# Beta24_SMD.net
KiCad netlist of a schematic drawn in EAGLE
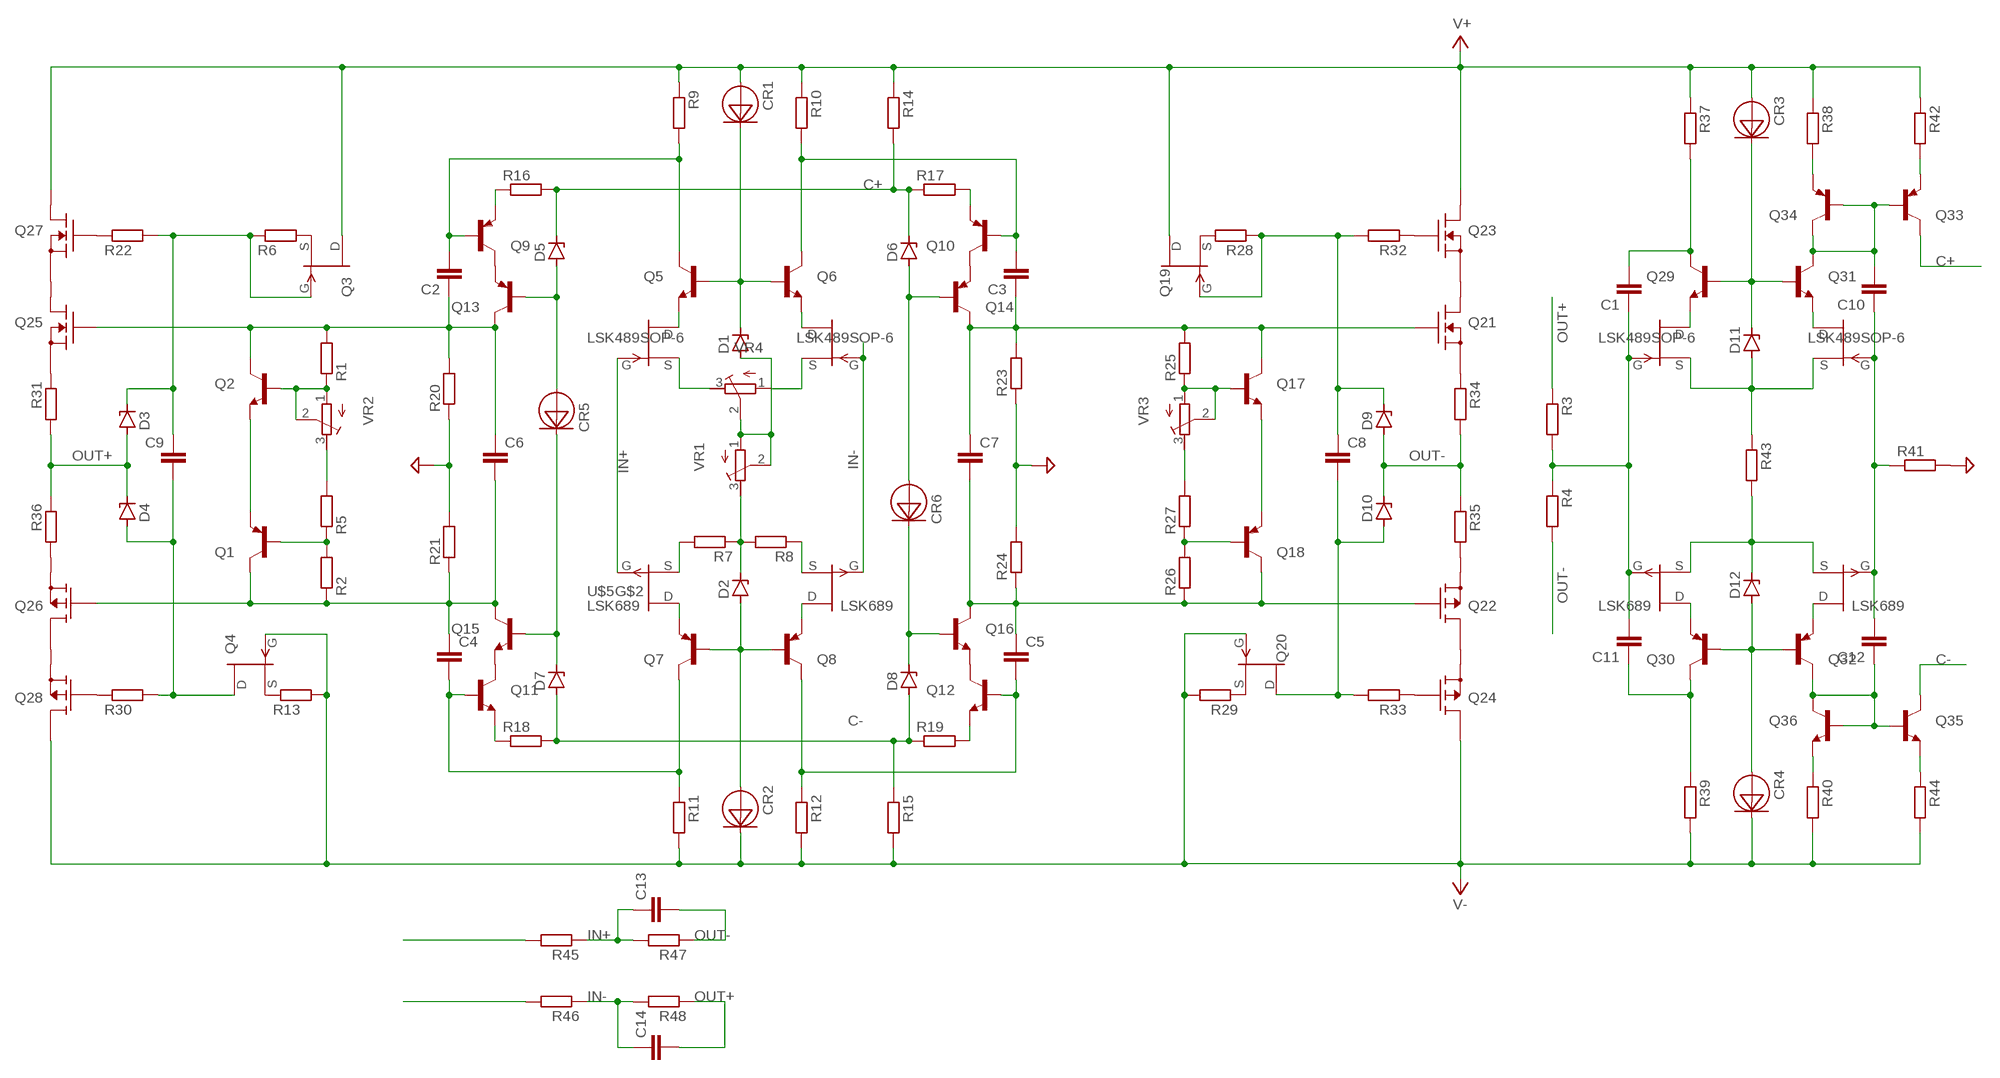
[diagram p0: schematic, sheet 1]

(export (version "E")
  (design (tool "Eeschema 10.0.6"))
  (components
    (comp (ref "C1")
      (value "C-EUC1206")
      (footprint "eagle-import:C1206")
      (libsource (lib "eagle-import") (part "C-EUC1206"))
    )
    (comp (ref "C2")
      (value "C-EUC1206")
      (footprint "eagle-import:C1206")
      (libsource (lib "eagle-import") (part "C-EUC1206"))
    )
    (comp (ref "C3")
      (value "C-EUC1206")
      (footprint "eagle-import:C1206")
      (libsource (lib "eagle-import") (part "C-EUC1206"))
    )
    (comp (ref "C4")
      (value "C-EUC1206")
      (footprint "eagle-import:C1206")
      (libsource (lib "eagle-import") (part "C-EUC1206"))
    )
    (comp (ref "C5")
      (value "C-EUC1206")
      (footprint "eagle-import:C1206")
      (libsource (lib "eagle-import") (part "C-EUC1206"))
    )
    (comp (ref "C6")
      (value "C-EUC1206")
      (footprint "eagle-import:C1206")
      (libsource (lib "eagle-import") (part "C-EUC1206"))
    )
    (comp (ref "C7")
      (value "C-EUC1206")
      (footprint "eagle-import:C1206")
      (libsource (lib "eagle-import") (part "C-EUC1206"))
    )
    (comp (ref "C8")
      (value "C-EUC1206")
      (footprint "eagle-import:C1206")
      (libsource (lib "eagle-import") (part "C-EUC1206"))
    )
    (comp (ref "C9")
      (value "C-EUC1206")
      (footprint "eagle-import:C1206")
      (libsource (lib "eagle-import") (part "C-EUC1206"))
    )
    (comp (ref "C10")
      (value "C-EUC1206")
      (footprint "eagle-import:C1206")
      (libsource (lib "eagle-import") (part "C-EUC1206"))
    )
    (comp (ref "C11")
      (value "C-EUC1206")
      (footprint "eagle-import:C1206")
      (libsource (lib "eagle-import") (part "C-EUC1206"))
    )
    (comp (ref "C12")
      (value "C-EUC1206")
      (footprint "eagle-import:C1206")
      (libsource (lib "eagle-import") (part "C-EUC1206"))
    )
    (comp (ref "C13")
      (value "C-EUC1206")
      (footprint "eagle-import:C1206")
      (libsource (lib "eagle-import") (part "C-EUC1206"))
    )
    (comp (ref "C14")
      (value "C-EUC1206")
      (footprint "eagle-import:C1206")
      (libsource (lib "eagle-import") (part "C-EUC1206"))
    )
    (comp (ref "CR1")
      (value "1N5283")
      (footprint "eagle-import:SMD")
      (libsource (lib "eagle-import") (part "1N5283"))
    )
    (comp (ref "CR2")
      (value "1N5283")
      (footprint "eagle-import:SMD")
      (libsource (lib "eagle-import") (part "1N5283"))
    )
    (comp (ref "CR3")
      (value "1N5283")
      (footprint "eagle-import:SMD")
      (libsource (lib "eagle-import") (part "1N5283"))
    )
    (comp (ref "CR4")
      (value "1N5283")
      (footprint "eagle-import:SMD")
      (libsource (lib "eagle-import") (part "1N5283"))
    )
    (comp (ref "CR5")
      (value "1N5283")
      (footprint "eagle-import:SMD")
      (libsource (lib "eagle-import") (part "1N5283"))
    )
    (comp (ref "CR6")
      (value "1N5283")
      (footprint "eagle-import:SMD")
      (libsource (lib "eagle-import") (part "1N5283"))
    )
    (comp (ref "D1")
      (value "ZENER-DIODESOD80C")
      (footprint "eagle-import:SOD80C")
      (libsource (lib "eagle-import") (part "ZENER-DIODESOD80C"))
    )
    (comp (ref "D2")
      (value "ZENER-DIODESOD80C")
      (footprint "eagle-import:SOD80C")
      (libsource (lib "eagle-import") (part "ZENER-DIODESOD80C"))
    )
    (comp (ref "D3")
      (value "ZENER-DIODESOD80C")
      (footprint "eagle-import:SOD80C")
      (libsource (lib "eagle-import") (part "ZENER-DIODESOD80C"))
    )
    (comp (ref "D4")
      (value "ZENER-DIODESOD80C")
      (footprint "eagle-import:SOD80C")
      (libsource (lib "eagle-import") (part "ZENER-DIODESOD80C"))
    )
    (comp (ref "D5")
      (value "ZENER-DIODESOD80C")
      (footprint "eagle-import:SOD80C")
      (libsource (lib "eagle-import") (part "ZENER-DIODESOD80C"))
    )
    (comp (ref "D6")
      (value "ZENER-DIODESOD80C")
      (footprint "eagle-import:SOD80C")
      (libsource (lib "eagle-import") (part "ZENER-DIODESOD80C"))
    )
    (comp (ref "D7")
      (value "ZENER-DIODESOD80C")
      (footprint "eagle-import:SOD80C")
      (libsource (lib "eagle-import") (part "ZENER-DIODESOD80C"))
    )
    (comp (ref "D8")
      (value "ZENER-DIODESOD80C")
      (footprint "eagle-import:SOD80C")
      (libsource (lib "eagle-import") (part "ZENER-DIODESOD80C"))
    )
    (comp (ref "D9")
      (value "ZENER-DIODESOD80C")
      (footprint "eagle-import:SOD80C")
      (libsource (lib "eagle-import") (part "ZENER-DIODESOD80C"))
    )
    (comp (ref "D10")
      (value "ZENER-DIODESOD80C")
      (footprint "eagle-import:SOD80C")
      (libsource (lib "eagle-import") (part "ZENER-DIODESOD80C"))
    )
    (comp (ref "D11")
      (value "ZENER-DIODESOD80C")
      (footprint "eagle-import:SOD80C")
      (libsource (lib "eagle-import") (part "ZENER-DIODESOD80C"))
    )
    (comp (ref "D12")
      (value "ZENER-DIODESOD80C")
      (footprint "eagle-import:SOD80C")
      (libsource (lib "eagle-import") (part "ZENER-DIODESOD80C"))
    )
    (comp (ref "Q1")
      (value "TRANSISTOR_BC858C-PNP-SOT23-BEC")
      (footprint "eagle-import:TRANSISTOR_SOT23-BEC")
      (libsource (lib "eagle-import") (part "TRANSISTOR_-PNP-SOT23-BECBC858C"))
    )
    (comp (ref "Q2")
      (value "TRANSISTOR_BC850-NPN-SOT23-BEC")
      (footprint "eagle-import:TRANSISTOR_SOT23-BEC")
      (libsource (lib "eagle-import") (part "TRANSISTOR_-NPN-SOT23-BECBC850"))
    )
    (comp (ref "Q3")
      (value "SST5486")
      (footprint "eagle-import:SOT23")
      (libsource (lib "eagle-import") (part "?548SST6"))
    )
    (comp (ref "Q4")
      (value "SST5486")
      (footprint "eagle-import:SOT23")
      (libsource (lib "eagle-import") (part "?548SST6"))
    )
    (comp (ref "Q5")
      (value "TRANSISTOR_BC850-NPN-SOT23-BEC")
      (footprint "eagle-import:TRANSISTOR_SOT23-BEC")
      (libsource (lib "eagle-import") (part "TRANSISTOR_-NPN-SOT23-BECBC850"))
    )
    (comp (ref "Q6")
      (value "TRANSISTOR_BC850-NPN-SOT23-BEC")
      (footprint "eagle-import:TRANSISTOR_SOT23-BEC")
      (libsource (lib "eagle-import") (part "TRANSISTOR_-NPN-SOT23-BECBC850"))
    )
    (comp (ref "Q7")
      (value "TRANSISTOR_BC858C-PNP-SOT23-BEC")
      (footprint "eagle-import:TRANSISTOR_SOT23-BEC")
      (libsource (lib "eagle-import") (part "TRANSISTOR_-PNP-SOT23-BECBC858C"))
    )
    (comp (ref "Q8")
      (value "TRANSISTOR_BC858C-PNP-SOT23-BEC")
      (footprint "eagle-import:TRANSISTOR_SOT23-BEC")
      (libsource (lib "eagle-import") (part "TRANSISTOR_-PNP-SOT23-BECBC858C"))
    )
    (comp (ref "Q9")
      (value "TRANSISTOR_BC858C-PNP-SOT23-BEC")
      (footprint "eagle-import:TRANSISTOR_SOT23-BEC")
      (libsource (lib "eagle-import") (part "TRANSISTOR_-PNP-SOT23-BECBC858C"))
    )
    (comp (ref "Q10")
      (value "TRANSISTOR_BC858C-PNP-SOT23-BEC")
      (footprint "eagle-import:TRANSISTOR_SOT23-BEC")
      (libsource (lib "eagle-import") (part "TRANSISTOR_-PNP-SOT23-BECBC858C"))
    )
    (comp (ref "Q11")
      (value "TRANSISTOR_BC850-NPN-SOT23-BEC")
      (footprint "eagle-import:TRANSISTOR_SOT23-BEC")
      (libsource (lib "eagle-import") (part "TRANSISTOR_-NPN-SOT23-BECBC850"))
    )
    (comp (ref "Q12")
      (value "TRANSISTOR_BC850-NPN-SOT23-BEC")
      (footprint "eagle-import:TRANSISTOR_SOT23-BEC")
      (libsource (lib "eagle-import") (part "TRANSISTOR_-NPN-SOT23-BECBC850"))
    )
    (comp (ref "Q13")
      (value "TRANSISTOR_BC858C-PNP-SOT23-BEC")
      (footprint "eagle-import:TRANSISTOR_SOT23-BEC")
      (libsource (lib "eagle-import") (part "TRANSISTOR_-PNP-SOT23-BECBC858C"))
    )
    (comp (ref "Q14")
      (value "TRANSISTOR_BC858C-PNP-SOT23-BEC")
      (footprint "eagle-import:TRANSISTOR_SOT23-BEC")
      (libsource (lib "eagle-import") (part "TRANSISTOR_-PNP-SOT23-BECBC858C"))
    )
    (comp (ref "Q15")
      (value "TRANSISTOR_BC850-NPN-SOT23-BEC")
      (footprint "eagle-import:TRANSISTOR_SOT23-BEC")
      (libsource (lib "eagle-import") (part "TRANSISTOR_-NPN-SOT23-BECBC850"))
    )
    (comp (ref "Q16")
      (value "TRANSISTOR_BC850-NPN-SOT23-BEC")
      (footprint "eagle-import:TRANSISTOR_SOT23-BEC")
      (libsource (lib "eagle-import") (part "TRANSISTOR_-NPN-SOT23-BECBC850"))
    )
    (comp (ref "Q17")
      (value "TRANSISTOR_BC850-NPN-SOT23-BEC")
      (footprint "eagle-import:TRANSISTOR_SOT23-BEC")
      (libsource (lib "eagle-import") (part "TRANSISTOR_-NPN-SOT23-BECBC850"))
    )
    (comp (ref "Q18")
      (value "TRANSISTOR_BC858C-PNP-SOT23-BEC")
      (footprint "eagle-import:TRANSISTOR_SOT23-BEC")
      (libsource (lib "eagle-import") (part "TRANSISTOR_-PNP-SOT23-BECBC858C"))
    )
    (comp (ref "Q19")
      (value "SST5486")
      (footprint "eagle-import:SOT23")
      (libsource (lib "eagle-import") (part "?548SST6"))
    )
    (comp (ref "Q20")
      (value "SST5486")
      (footprint "eagle-import:SOT23")
      (libsource (lib "eagle-import") (part "?548SST6"))
    )
    (comp (ref "Q21")
      (value "IRFZ24N")
      (footprint "eagle-import:TO220V")
      (libsource (lib "eagle-import") (part "IRFZ24N"))
    )
    (comp (ref "Q22")
      (value "IRFZ34N")
      (footprint "eagle-import:TO220V")
      (libsource (lib "eagle-import") (part "IRFZ34N"))
    )
    (comp (ref "Q23")
      (value "IRFZ24N")
      (footprint "eagle-import:TO220V")
      (libsource (lib "eagle-import") (part "IRFZ24N"))
    )
    (comp (ref "Q24")
      (value "IRFZ34N")
      (footprint "eagle-import:TO220V")
      (libsource (lib "eagle-import") (part "IRFZ34N"))
    )
    (comp (ref "Q25")
      (value "IRFZ24N")
      (footprint "eagle-import:TO220V")
      (libsource (lib "eagle-import") (part "IRFZ24N"))
    )
    (comp (ref "Q26")
      (value "IRFZ34N")
      (footprint "eagle-import:TO220V")
      (libsource (lib "eagle-import") (part "IRFZ34N"))
    )
    (comp (ref "Q27")
      (value "IRFZ24N")
      (footprint "eagle-import:TO220V")
      (libsource (lib "eagle-import") (part "IRFZ24N"))
    )
    (comp (ref "Q28")
      (value "IRFZ34N")
      (footprint "eagle-import:TO220V")
      (libsource (lib "eagle-import") (part "IRFZ34N"))
    )
    (comp (ref "Q29")
      (value "TRANSISTOR_BC850-NPN-SOT23-BEC")
      (footprint "eagle-import:TRANSISTOR_SOT23-BEC")
      (libsource (lib "eagle-import") (part "TRANSISTOR_-NPN-SOT23-BECBC850"))
    )
    (comp (ref "Q30")
      (value "TRANSISTOR_BC858C-PNP-SOT23-BEC")
      (footprint "eagle-import:TRANSISTOR_SOT23-BEC")
      (libsource (lib "eagle-import") (part "TRANSISTOR_-PNP-SOT23-BECBC858C"))
    )
    (comp (ref "Q31")
      (value "TRANSISTOR_BC850-NPN-SOT23-BEC")
      (footprint "eagle-import:TRANSISTOR_SOT23-BEC")
      (libsource (lib "eagle-import") (part "TRANSISTOR_-NPN-SOT23-BECBC850"))
    )
    (comp (ref "Q32")
      (value "TRANSISTOR_BC858C-PNP-SOT23-BEC")
      (footprint "eagle-import:TRANSISTOR_SOT23-BEC")
      (libsource (lib "eagle-import") (part "TRANSISTOR_-PNP-SOT23-BECBC858C"))
    )
    (comp (ref "Q33")
      (value "TRANSISTOR_BC858C-PNP-SOT23-BEC")
      (footprint "eagle-import:TRANSISTOR_SOT23-BEC")
      (libsource (lib "eagle-import") (part "TRANSISTOR_-PNP-SOT23-BECBC858C"))
    )
    (comp (ref "Q34")
      (value "TRANSISTOR_BC858C-PNP-SOT23-BEC")
      (footprint "eagle-import:TRANSISTOR_SOT23-BEC")
      (libsource (lib "eagle-import") (part "TRANSISTOR_-PNP-SOT23-BECBC858C"))
    )
    (comp (ref "Q35")
      (value "TRANSISTOR_BC850-NPN-SOT23-BEC")
      (footprint "eagle-import:TRANSISTOR_SOT23-BEC")
      (libsource (lib "eagle-import") (part "TRANSISTOR_-NPN-SOT23-BECBC850"))
    )
    (comp (ref "Q36")
      (value "TRANSISTOR_BC850-NPN-SOT23-BEC")
      (footprint "eagle-import:TRANSISTOR_SOT23-BEC")
      (libsource (lib "eagle-import") (part "TRANSISTOR_-NPN-SOT23-BECBC850"))
    )
    (comp (ref "R1")
      (value "R-EU_MELF0204W")
      (footprint "eagle-import:MINI_MELF-0204W")
      (libsource (lib "eagle-import") (part "R-EU_MELF0204W"))
    )
    (comp (ref "R2")
      (value "R-EU_MELF0204W")
      (footprint "eagle-import:MINI_MELF-0204W")
      (libsource (lib "eagle-import") (part "R-EU_MELF0204W"))
    )
    (comp (ref "R3")
      (value "R-EU_MELF0204W")
      (footprint "eagle-import:MINI_MELF-0204W")
      (libsource (lib "eagle-import") (part "R-EU_MELF0204W"))
    )
    (comp (ref "R4")
      (value "R-EU_MELF0204W")
      (footprint "eagle-import:MINI_MELF-0204W")
      (libsource (lib "eagle-import") (part "R-EU_MELF0204W"))
    )
    (comp (ref "R5")
      (value "R-EU_MELF0204W")
      (footprint "eagle-import:MINI_MELF-0204W")
      (libsource (lib "eagle-import") (part "R-EU_MELF0204W"))
    )
    (comp (ref "R6")
      (value "R-EU_MELF0204W")
      (footprint "eagle-import:MINI_MELF-0204W")
      (libsource (lib "eagle-import") (part "R-EU_MELF0204W"))
    )
    (comp (ref "R7")
      (value "R-EU_MELF0204W")
      (footprint "eagle-import:MINI_MELF-0204W")
      (libsource (lib "eagle-import") (part "R-EU_MELF0204W"))
    )
    (comp (ref "R8")
      (value "R-EU_MELF0204W")
      (footprint "eagle-import:MINI_MELF-0204W")
      (libsource (lib "eagle-import") (part "R-EU_MELF0204W"))
    )
    (comp (ref "R9")
      (value "R-EU_MELF0204W")
      (footprint "eagle-import:MINI_MELF-0204W")
      (libsource (lib "eagle-import") (part "R-EU_MELF0204W"))
    )
    (comp (ref "R10")
      (value "R-EU_MELF0204W")
      (footprint "eagle-import:MINI_MELF-0204W")
      (libsource (lib "eagle-import") (part "R-EU_MELF0204W"))
    )
    (comp (ref "R11")
      (value "R-EU_MELF0204W")
      (footprint "eagle-import:MINI_MELF-0204W")
      (libsource (lib "eagle-import") (part "R-EU_MELF0204W"))
    )
    (comp (ref "R12")
      (value "R-EU_MELF0204W")
      (footprint "eagle-import:MINI_MELF-0204W")
      (libsource (lib "eagle-import") (part "R-EU_MELF0204W"))
    )
    (comp (ref "R13")
      (value "R-EU_MELF0204W")
      (footprint "eagle-import:MINI_MELF-0204W")
      (libsource (lib "eagle-import") (part "R-EU_MELF0204W"))
    )
    (comp (ref "R14")
      (value "R-EU_MELF0204W")
      (footprint "eagle-import:MINI_MELF-0204W")
      (libsource (lib "eagle-import") (part "R-EU_MELF0204W"))
    )
    (comp (ref "R15")
      (value "R-EU_MELF0204W")
      (footprint "eagle-import:MINI_MELF-0204W")
      (libsource (lib "eagle-import") (part "R-EU_MELF0204W"))
    )
    (comp (ref "R16")
      (value "R-EU_MELF0204W")
      (footprint "eagle-import:MINI_MELF-0204W")
      (libsource (lib "eagle-import") (part "R-EU_MELF0204W"))
    )
    (comp (ref "R17")
      (value "R-EU_MELF0204W")
      (footprint "eagle-import:MINI_MELF-0204W")
      (libsource (lib "eagle-import") (part "R-EU_MELF0204W"))
    )
    (comp (ref "R18")
      (value "R-EU_MELF0204W")
      (footprint "eagle-import:MINI_MELF-0204W")
      (libsource (lib "eagle-import") (part "R-EU_MELF0204W"))
    )
    (comp (ref "R19")
      (value "R-EU_MELF0204W")
      (footprint "eagle-import:MINI_MELF-0204W")
      (libsource (lib "eagle-import") (part "R-EU_MELF0204W"))
    )
    (comp (ref "R20")
      (value "R-EU_MELF0204W")
      (footprint "eagle-import:MINI_MELF-0204W")
      (libsource (lib "eagle-import") (part "R-EU_MELF0204W"))
    )
    (comp (ref "R21")
      (value "R-EU_MELF0204W")
      (footprint "eagle-import:MINI_MELF-0204W")
      (libsource (lib "eagle-import") (part "R-EU_MELF0204W"))
    )
    (comp (ref "R22")
      (value "R-EU_MELF0204W")
      (footprint "eagle-import:MINI_MELF-0204W")
      (libsource (lib "eagle-import") (part "R-EU_MELF0204W"))
    )
    (comp (ref "R23")
      (value "R-EU_MELF0204W")
      (footprint "eagle-import:MINI_MELF-0204W")
      (libsource (lib "eagle-import") (part "R-EU_MELF0204W"))
    )
    (comp (ref "R24")
      (value "R-EU_MELF0204W")
      (footprint "eagle-import:MINI_MELF-0204W")
      (libsource (lib "eagle-import") (part "R-EU_MELF0204W"))
    )
    (comp (ref "R25")
      (value "R-EU_MELF0204W")
      (footprint "eagle-import:MINI_MELF-0204W")
      (libsource (lib "eagle-import") (part "R-EU_MELF0204W"))
    )
    (comp (ref "R26")
      (value "R-EU_MELF0204W")
      (footprint "eagle-import:MINI_MELF-0204W")
      (libsource (lib "eagle-import") (part "R-EU_MELF0204W"))
    )
    (comp (ref "R27")
      (value "R-EU_MELF0204W")
      (footprint "eagle-import:MINI_MELF-0204W")
      (libsource (lib "eagle-import") (part "R-EU_MELF0204W"))
    )
    (comp (ref "R28")
      (value "R-EU_MELF0204W")
      (footprint "eagle-import:MINI_MELF-0204W")
      (libsource (lib "eagle-import") (part "R-EU_MELF0204W"))
    )
    (comp (ref "R29")
      (value "R-EU_MELF0204W")
      (footprint "eagle-import:MINI_MELF-0204W")
      (libsource (lib "eagle-import") (part "R-EU_MELF0204W"))
    )
    (comp (ref "R30")
      (value "R-EU_MELF0204W")
      (footprint "eagle-import:MINI_MELF-0204W")
      (libsource (lib "eagle-import") (part "R-EU_MELF0204W"))
    )
    (comp (ref "R31")
      (value "R-EU_0617/17")
      (footprint "eagle-import:0617_17")
      (libsource (lib "eagle-import") (part "R-EU_0617/17"))
    )
    (comp (ref "R32")
      (value "R-EU_MELF0204W")
      (footprint "eagle-import:MINI_MELF-0204W")
      (libsource (lib "eagle-import") (part "R-EU_MELF0204W"))
    )
    (comp (ref "R33")
      (value "R-EU_MELF0204W")
      (footprint "eagle-import:MINI_MELF-0204W")
      (libsource (lib "eagle-import") (part "R-EU_MELF0204W"))
    )
    (comp (ref "R34")
      (value "R-EU_0617/17")
      (footprint "eagle-import:0617_17")
      (libsource (lib "eagle-import") (part "R-EU_0617/17"))
    )
    (comp (ref "R35")
      (value "R-EU_0617/17")
      (footprint "eagle-import:0617_17")
      (libsource (lib "eagle-import") (part "R-EU_0617/17"))
    )
    (comp (ref "R36")
      (value "R-EU_0617/17")
      (footprint "eagle-import:0617_17")
      (libsource (lib "eagle-import") (part "R-EU_0617/17"))
    )
    (comp (ref "R37")
      (value "R-EU_MELF0204W")
      (footprint "eagle-import:MINI_MELF-0204W")
      (libsource (lib "eagle-import") (part "R-EU_MELF0204W"))
    )
    (comp (ref "R38")
      (value "R-EU_MELF0204W")
      (footprint "eagle-import:MINI_MELF-0204W")
      (libsource (lib "eagle-import") (part "R-EU_MELF0204W"))
    )
    (comp (ref "R39")
      (value "R-EU_MELF0204W")
      (footprint "eagle-import:MINI_MELF-0204W")
      (libsource (lib "eagle-import") (part "R-EU_MELF0204W"))
    )
    (comp (ref "R40")
      (value "R-EU_MELF0204W")
      (footprint "eagle-import:MINI_MELF-0204W")
      (libsource (lib "eagle-import") (part "R-EU_MELF0204W"))
    )
    (comp (ref "R41")
      (value "R-EU_MELF0204W")
      (footprint "eagle-import:MINI_MELF-0204W")
      (libsource (lib "eagle-import") (part "R-EU_MELF0204W"))
    )
    (comp (ref "R42")
      (value "R-EU_MELF0204W")
      (footprint "eagle-import:MINI_MELF-0204W")
      (libsource (lib "eagle-import") (part "R-EU_MELF0204W"))
    )
    (comp (ref "R43")
      (value "R-EU_MELF0204W")
      (footprint "eagle-import:MINI_MELF-0204W")
      (libsource (lib "eagle-import") (part "R-EU_MELF0204W"))
    )
    (comp (ref "R44")
      (value "R-EU_MELF0204W")
      (footprint "eagle-import:MINI_MELF-0204W")
      (libsource (lib "eagle-import") (part "R-EU_MELF0204W"))
    )
    (comp (ref "R45")
      (value "R-EU_MELF0204W")
      (footprint "eagle-import:MINI_MELF-0204W")
      (libsource (lib "eagle-import") (part "R-EU_MELF0204W"))
    )
    (comp (ref "R46")
      (value "R-EU_MELF0204W")
      (footprint "eagle-import:MINI_MELF-0204W")
      (libsource (lib "eagle-import") (part "R-EU_MELF0204W"))
    )
    (comp (ref "R47")
      (value "R-EU_MELF0204W")
      (footprint "eagle-import:MINI_MELF-0204W")
      (libsource (lib "eagle-import") (part "R-EU_MELF0204W"))
    )
    (comp (ref "R48")
      (value "R-EU_MELF0204W")
      (footprint "eagle-import:MINI_MELF-0204W")
      (libsource (lib "eagle-import") (part "R-EU_MELF0204W"))
    )
    (comp (ref "U$1")
      (value "LSK489SOP-6")
      (footprint "eagle-import:SOT-23-6")
      (libsource (lib "eagle-import") (part "LSK489SOP-6"))
    )
    (comp (ref "U$3")
      (value "LSK489SOP-6")
      (footprint "eagle-import:SOT-23-6")
      (libsource (lib "eagle-import") (part "LSK489SOP-6"))
    )
    (comp (ref "U$4")
      (value "LSK689")
      (footprint "eagle-import:SOT-23-6")
      (libsource (lib "eagle-import") (part "LSK689"))
    )
    (comp (ref "U$5")
      (value "LSK689")
      (footprint "eagle-import:SOT-23-6")
      (libsource (lib "eagle-import") (part "LSK689"))
    )
    (comp (ref "VR1")
      (value "R-TRIMM3296W")
      (footprint "eagle-import:RTRIM3296W")
      (libsource (lib "eagle-import") (part "R-TRIMM3296W"))
    )
    (comp (ref "VR2")
      (value "R-TRIMM3296W")
      (footprint "eagle-import:RTRIM3296W")
      (libsource (lib "eagle-import") (part "R-TRIMM3296W"))
    )
    (comp (ref "VR3")
      (value "R-TRIMM3296W")
      (footprint "eagle-import:RTRIM3296W")
      (libsource (lib "eagle-import") (part "R-TRIMM3296W"))
    )
    (comp (ref "VR4")
      (value "R-TRIMM3296W")
      (footprint "eagle-import:RTRIM3296W")
      (libsource (lib "eagle-import") (part "R-TRIMM3296W"))
    )
  )
  (nets
    (net (code "1") (name "/C+") (class "Default")
      (node (ref "D5") (pin "C") (pinfunction "C_C") (pintype "passive"))
      (node (ref "D6") (pin "C") (pinfunction "C_C") (pintype "passive"))
      (node (ref "Q33") (pin "C") (pinfunction "C_C") (pintype "passive"))
      (node (ref "R14") (pin "2") (pinfunction "2_2") (pintype "passive"))
      (node (ref "R16") (pin "2") (pinfunction "2_2") (pintype "passive"))
      (node (ref "R17") (pin "1") (pinfunction "1_1") (pintype "passive"))
    )
    (net (code "2") (name "/C-") (class "Default")
      (node (ref "D7") (pin "A") (pinfunction "A_A") (pintype "passive"))
      (node (ref "D8") (pin "A") (pinfunction "A_A") (pintype "passive"))
      (node (ref "Q35") (pin "C") (pinfunction "C_C") (pintype "passive"))
      (node (ref "R15") (pin "1") (pinfunction "1_1") (pintype "passive"))
      (node (ref "R18") (pin "2") (pinfunction "2_2") (pintype "passive"))
      (node (ref "R19") (pin "1") (pinfunction "1_1") (pintype "passive"))
    )
    (net (code "3") (name "/IN+") (class "Default")
      (node (ref "C13") (pin "1") (pinfunction "1_1") (pintype "passive"))
      (node (ref "R45") (pin "1") (pinfunction "1_1") (pintype "passive"))
      (node (ref "R47") (pin "2") (pinfunction "2_2") (pintype "passive"))
      (node (ref "U$1") (pin "1") (pinfunction "G_1") (pintype "passive"))
      (node (ref "U$5") (pin "4") (pinfunction "G_4") (pintype "passive"))
    )
    (net (code "4") (name "/IN-") (class "Default")
      (node (ref "C14") (pin "1") (pinfunction "1_1") (pintype "passive"))
      (node (ref "R46") (pin "1") (pinfunction "1_1") (pintype "passive"))
      (node (ref "R48") (pin "2") (pinfunction "2_2") (pintype "passive"))
      (node (ref "U$1") (pin "4") (pinfunction "G_4") (pintype "passive"))
      (node (ref "U$5") (pin "1") (pinfunction "G_1") (pintype "passive"))
    )
    (net (code "5") (name "/OUT+") (class "Default")
      (node (ref "C14") (pin "2") (pinfunction "2_2") (pintype "passive"))
      (node (ref "D3") (pin "A") (pinfunction "A_A") (pintype "passive"))
      (node (ref "D4") (pin "C") (pinfunction "C_C") (pintype "passive"))
      (node (ref "R3") (pin "1") (pinfunction "1_1") (pintype "passive"))
      (node (ref "R31") (pin "2") (pinfunction "2_2") (pintype "passive"))
      (node (ref "R36") (pin "1") (pinfunction "1_1") (pintype "passive"))
      (node (ref "R48") (pin "1") (pinfunction "1_1") (pintype "passive"))
    )
    (net (code "6") (name "/OUT-") (class "Default")
      (node (ref "C13") (pin "2") (pinfunction "2_2") (pintype "passive"))
      (node (ref "D10") (pin "C") (pinfunction "C_C") (pintype "passive"))
      (node (ref "D9") (pin "A") (pinfunction "A_A") (pintype "passive"))
      (node (ref "R34") (pin "2") (pinfunction "2_2") (pintype "passive"))
      (node (ref "R35") (pin "1") (pinfunction "1_1") (pintype "passive"))
      (node (ref "R4") (pin "2") (pinfunction "2_2") (pintype "passive"))
      (node (ref "R47") (pin "1") (pinfunction "1_1") (pintype "passive"))
    )
    (net (code "7") (name "GND") (class "Default")
      (node (ref "R20") (pin "1") (pinfunction "1_1") (pintype "passive"))
      (node (ref "R21") (pin "2") (pinfunction "2_2") (pintype "passive"))
      (node (ref "R23") (pin "1") (pinfunction "1_1") (pintype "passive"))
      (node (ref "R24") (pin "2") (pinfunction "2_2") (pintype "passive"))
      (node (ref "R41") (pin "2") (pinfunction "2_2") (pintype "passive"))
    )
    (net (code "8") (name "Net-(C1-Pad2)") (class "Default")
      (node (ref "C1") (pin "2") (pinfunction "2_2") (pintype "passive"))
      (node (ref "Q29") (pin "C") (pinfunction "C_C") (pintype "passive"))
      (node (ref "R37") (pin "2") (pinfunction "2_2") (pintype "passive"))
    )
    (net (code "9") (name "Net-(C2-Pad2)") (class "Default")
      (node (ref "C2") (pin "2") (pinfunction "2_2") (pintype "passive"))
      (node (ref "Q5") (pin "C") (pinfunction "C_C") (pintype "passive"))
      (node (ref "Q9") (pin "B") (pinfunction "B_B") (pintype "passive"))
      (node (ref "R9") (pin "2") (pinfunction "2_2") (pintype "passive"))
    )
    (net (code "10") (name "Net-(C3-Pad2)") (class "Default")
      (node (ref "C3") (pin "2") (pinfunction "2_2") (pintype "passive"))
      (node (ref "Q10") (pin "B") (pinfunction "B_B") (pintype "passive"))
      (node (ref "Q6") (pin "C") (pinfunction "C_C") (pintype "passive"))
      (node (ref "R10") (pin "2") (pinfunction "2_2") (pintype "passive"))
    )
    (net (code "11") (name "Net-(C4-Pad2)") (class "Default")
      (node (ref "C4") (pin "2") (pinfunction "2_2") (pintype "passive"))
      (node (ref "Q11") (pin "B") (pinfunction "B_B") (pintype "passive"))
      (node (ref "Q7") (pin "C") (pinfunction "C_C") (pintype "passive"))
      (node (ref "R11") (pin "1") (pinfunction "1_1") (pintype "passive"))
    )
    (net (code "12") (name "Net-(C5-Pad2)") (class "Default")
      (node (ref "C5") (pin "2") (pinfunction "2_2") (pintype "passive"))
      (node (ref "Q12") (pin "B") (pinfunction "B_B") (pintype "passive"))
      (node (ref "Q8") (pin "C") (pinfunction "C_C") (pintype "passive"))
      (node (ref "R12") (pin "1") (pinfunction "1_1") (pintype "passive"))
    )
    (net (code "13") (name "Net-(C10-Pad2)") (class "Default")
      (node (ref "C10") (pin "2") (pinfunction "2_2") (pintype "passive"))
      (node (ref "Q31") (pin "C") (pinfunction "C_C") (pintype "passive"))
      (node (ref "Q33") (pin "B") (pinfunction "B_B") (pintype "passive"))
      (node (ref "Q34") (pin "B") (pinfunction "B_B") (pintype "passive"))
      (node (ref "Q34") (pin "C") (pinfunction "C_C") (pintype "passive"))
    )
    (net (code "14") (name "Net-(C11-Pad1)") (class "Default")
      (node (ref "C11") (pin "1") (pinfunction "1_1") (pintype "passive"))
      (node (ref "Q30") (pin "C") (pinfunction "C_C") (pintype "passive"))
      (node (ref "R39") (pin "1") (pinfunction "1_1") (pintype "passive"))
    )
    (net (code "15") (name "Net-(C12-Pad1)") (class "Default")
      (node (ref "C12") (pin "1") (pinfunction "1_1") (pintype "passive"))
      (node (ref "Q32") (pin "C") (pinfunction "C_C") (pintype "passive"))
      (node (ref "Q35") (pin "B") (pinfunction "B_B") (pintype "passive"))
      (node (ref "Q36") (pin "B") (pinfunction "B_B") (pintype "passive"))
      (node (ref "Q36") (pin "C") (pinfunction "C_C") (pintype "passive"))
    )
    (net (code "16") (name "Net-(CR1-PadCATHODE)") (class "Default")
      (node (ref "CR1") (pin "CATHODE") (pinfunction "CATHODE_CATHODE") (pintype "passive"))
      (node (ref "D1") (pin "C") (pinfunction "C_C") (pintype "passive"))
      (node (ref "Q5") (pin "B") (pinfunction "B_B") (pintype "passive"))
      (node (ref "Q6") (pin "B") (pinfunction "B_B") (pintype "passive"))
    )
    (net (code "17") (name "Net-(CR2-PadANODE)") (class "Default")
      (node (ref "CR2") (pin "ANODE") (pinfunction "ANODE_ANODE") (pintype "passive"))
      (node (ref "D2") (pin "A") (pinfunction "A_A") (pintype "passive"))
      (node (ref "Q7") (pin "B") (pinfunction "B_B") (pintype "passive"))
      (node (ref "Q8") (pin "B") (pinfunction "B_B") (pintype "passive"))
    )
    (net (code "18") (name "Net-(CR3-PadCATHODE)") (class "Default")
      (node (ref "CR3") (pin "CATHODE") (pinfunction "CATHODE_CATHODE") (pintype "passive"))
      (node (ref "D11") (pin "C") (pinfunction "C_C") (pintype "passive"))
      (node (ref "Q29") (pin "B") (pinfunction "B_B") (pintype "passive"))
      (node (ref "Q31") (pin "B") (pinfunction "B_B") (pintype "passive"))
    )
    (net (code "19") (name "Net-(CR4-PadANODE)") (class "Default")
      (node (ref "CR4") (pin "ANODE") (pinfunction "ANODE_ANODE") (pintype "passive"))
      (node (ref "D12") (pin "A") (pinfunction "A_A") (pintype "passive"))
      (node (ref "Q30") (pin "B") (pinfunction "B_B") (pintype "passive"))
      (node (ref "Q32") (pin "B") (pinfunction "B_B") (pintype "passive"))
    )
    (net (code "20") (name "Net-(CR5-PadANODE)") (class "Default")
      (node (ref "CR5") (pin "ANODE") (pinfunction "ANODE_ANODE") (pintype "passive"))
      (node (ref "D5") (pin "A") (pinfunction "A_A") (pintype "passive"))
      (node (ref "Q13") (pin "B") (pinfunction "B_B") (pintype "passive"))
    )
    (net (code "21") (name "Net-(CR5-PadCATHODE)") (class "Default")
      (node (ref "CR5") (pin "CATHODE") (pinfunction "CATHODE_CATHODE") (pintype "passive"))
      (node (ref "D7") (pin "C") (pinfunction "C_C") (pintype "passive"))
      (node (ref "Q15") (pin "B") (pinfunction "B_B") (pintype "passive"))
    )
    (net (code "22") (name "Net-(CR6-PadANODE)") (class "Default")
      (node (ref "CR6") (pin "ANODE") (pinfunction "ANODE_ANODE") (pintype "passive"))
      (node (ref "D6") (pin "A") (pinfunction "A_A") (pintype "passive"))
      (node (ref "Q14") (pin "B") (pinfunction "B_B") (pintype "passive"))
    )
    (net (code "23") (name "Net-(CR6-PadCATHODE)") (class "Default")
      (node (ref "CR6") (pin "CATHODE") (pinfunction "CATHODE_CATHODE") (pintype "passive"))
      (node (ref "D8") (pin "C") (pinfunction "C_C") (pintype "passive"))
      (node (ref "Q16") (pin "B") (pinfunction "B_B") (pintype "passive"))
    )
    (net (code "24") (name "Net-(Q1-PadB)") (class "Default")
      (node (ref "Q1") (pin "B") (pinfunction "B_B") (pintype "passive"))
      (node (ref "R2") (pin "2") (pinfunction "2_2") (pintype "passive"))
      (node (ref "R5") (pin "1") (pinfunction "1_1") (pintype "passive"))
    )
    (net (code "25") (name "Net-(Q1-PadE)") (class "Default")
      (node (ref "Q1") (pin "E") (pinfunction "E_E") (pintype "passive"))
      (node (ref "Q2") (pin "E") (pinfunction "E_E") (pintype "passive"))
    )
    (net (code "26") (name "Net-(Q3-G)") (class "Default")
      (node (ref "C9") (pin "1") (pinfunction "1_1") (pintype "passive"))
      (node (ref "D3") (pin "C") (pinfunction "C_C") (pintype "passive"))
      (node (ref "Q3") (pin "3") (pinfunction "G_3") (pintype "passive"))
      (node (ref "R22") (pin "2") (pinfunction "2_2") (pintype "passive"))
      (node (ref "R6") (pin "1") (pinfunction "1_1") (pintype "passive"))
    )
    (net (code "27") (name "Net-(Q3-S)") (class "Default")
      (node (ref "Q3") (pin "2") (pinfunction "S_2") (pintype "passive"))
      (node (ref "R6") (pin "2") (pinfunction "2_2") (pintype "passive"))
    )
    (net (code "28") (name "Net-(Q4-D)") (class "Default")
      (node (ref "C9") (pin "2") (pinfunction "2_2") (pintype "passive"))
      (node (ref "D4") (pin "A") (pinfunction "A_A") (pintype "passive"))
      (node (ref "Q4") (pin "1") (pinfunction "D_1") (pintype "passive"))
      (node (ref "R30") (pin "2") (pinfunction "2_2") (pintype "passive"))
    )
    (net (code "29") (name "Net-(Q4-S)") (class "Default")
      (node (ref "Q4") (pin "2") (pinfunction "S_2") (pintype "passive"))
      (node (ref "R13") (pin "1") (pinfunction "1_1") (pintype "passive"))
    )
    (net (code "30") (name "Net-(Q9-PadE)") (class "Default")
      (node (ref "Q9") (pin "E") (pinfunction "E_E") (pintype "passive"))
      (node (ref "R16") (pin "1") (pinfunction "1_1") (pintype "passive"))
    )
    (net (code "31") (name "Net-(Q10-PadC)") (class "Default")
      (node (ref "Q10") (pin "C") (pinfunction "C_C") (pintype "passive"))
      (node (ref "Q14") (pin "E") (pinfunction "E_E") (pintype "passive"))
    )
    (net (code "32") (name "Net-(Q10-PadE)") (class "Default")
      (node (ref "Q10") (pin "E") (pinfunction "E_E") (pintype "passive"))
      (node (ref "R17") (pin "2") (pinfunction "2_2") (pintype "passive"))
    )
    (net (code "33") (name "Net-(Q11-PadC)") (class "Default")
      (node (ref "Q11") (pin "C") (pinfunction "C_C") (pintype "passive"))
      (node (ref "Q15") (pin "E") (pinfunction "E_E") (pintype "passive"))
    )
    (net (code "34") (name "Net-(Q11-PadE)") (class "Default")
      (node (ref "Q11") (pin "E") (pinfunction "E_E") (pintype "passive"))
      (node (ref "R18") (pin "1") (pinfunction "1_1") (pintype "passive"))
    )
    (net (code "35") (name "Net-(Q12-PadC)") (class "Default")
      (node (ref "Q12") (pin "C") (pinfunction "C_C") (pintype "passive"))
      (node (ref "Q16") (pin "E") (pinfunction "E_E") (pintype "passive"))
    )
    (net (code "36") (name "Net-(Q12-PadE)") (class "Default")
      (node (ref "Q12") (pin "E") (pinfunction "E_E") (pintype "passive"))
      (node (ref "R19") (pin "2") (pinfunction "2_2") (pintype "passive"))
    )
    (net (code "37") (name "Net-(Q13-PadE)") (class "Default")
      (node (ref "Q13") (pin "E") (pinfunction "E_E") (pintype "passive"))
      (node (ref "Q9") (pin "C") (pinfunction "C_C") (pintype "passive"))
    )
    (net (code "38") (name "Net-(Q17-PadE)") (class "Default")
      (node (ref "Q17") (pin "E") (pinfunction "E_E") (pintype "passive"))
      (node (ref "Q18") (pin "E") (pinfunction "E_E") (pintype "passive"))
    )
    (net (code "39") (name "Net-(Q18-PadB)") (class "Default")
      (node (ref "Q18") (pin "B") (pinfunction "B_B") (pintype "passive"))
      (node (ref "R26") (pin "2") (pinfunction "2_2") (pintype "passive"))
      (node (ref "R27") (pin "1") (pinfunction "1_1") (pintype "passive"))
    )
    (net (code "40") (name "Net-(Q19-G)") (class "Default")
      (node (ref "C8") (pin "1") (pinfunction "1_1") (pintype "passive"))
      (node (ref "D9") (pin "C") (pinfunction "C_C") (pintype "passive"))
      (node (ref "Q19") (pin "3") (pinfunction "G_3") (pintype "passive"))
      (node (ref "R28") (pin "1") (pinfunction "1_1") (pintype "passive"))
      (node (ref "R32") (pin "2") (pinfunction "2_2") (pintype "passive"))
    )
    (net (code "41") (name "Net-(Q19-S)") (class "Default")
      (node (ref "Q19") (pin "2") (pinfunction "S_2") (pintype "passive"))
      (node (ref "R28") (pin "2") (pinfunction "2_2") (pintype "passive"))
    )
    (net (code "42") (name "Net-(Q20-D)") (class "Default")
      (node (ref "C8") (pin "2") (pinfunction "2_2") (pintype "passive"))
      (node (ref "D10") (pin "A") (pinfunction "A_A") (pintype "passive"))
      (node (ref "Q20") (pin "1") (pinfunction "D_1") (pintype "passive"))
      (node (ref "R33") (pin "2") (pinfunction "2_2") (pintype "passive"))
    )
    (net (code "43") (name "Net-(Q20-S)") (class "Default")
      (node (ref "Q20") (pin "2") (pinfunction "S_2") (pintype "passive"))
      (node (ref "R29") (pin "1") (pinfunction "1_1") (pintype "passive"))
    )
    (net (code "44") (name "Net-(Q21-D)") (class "Default")
      (node (ref "Q21") (pin "2") (pinfunction "D_2") (pintype "passive"))
      (node (ref "Q23") (pin "3") (pinfunction "S_3") (pintype "passive"))
    )
    (net (code "45") (name "Net-(Q21-G)") (class "Default")
      (node (ref "C3") (pin "1") (pinfunction "1_1") (pintype "passive"))
      (node (ref "C7") (pin "1") (pinfunction "1_1") (pintype "passive"))
      (node (ref "Q14") (pin "C") (pinfunction "C_C") (pintype "passive"))
      (node (ref "Q17") (pin "C") (pinfunction "C_C") (pintype "passive"))
      (node (ref "Q21") (pin "1") (pinfunction "G_1") (pintype "passive"))
      (node (ref "R23") (pin "2") (pinfunction "2_2") (pintype "passive"))
      (node (ref "R25") (pin "2") (pinfunction "2_2") (pintype "passive"))
    )
    (net (code "46") (name "Net-(Q21-S)") (class "Default")
      (node (ref "Q21") (pin "3") (pinfunction "S_3") (pintype "passive"))
      (node (ref "R34") (pin "1") (pinfunction "1_1") (pintype "passive"))
    )
    (net (code "47") (name "Net-(Q22-D)") (class "Default")
      (node (ref "Q22") (pin "2") (pinfunction "D_2") (pintype "passive"))
      (node (ref "Q24") (pin "3") (pinfunction "S_3") (pintype "passive"))
    )
    (net (code "48") (name "Net-(Q22-G)") (class "Default")
      (node (ref "C5") (pin "1") (pinfunction "1_1") (pintype "passive"))
      (node (ref "C7") (pin "2") (pinfunction "2_2") (pintype "passive"))
      (node (ref "Q16") (pin "C") (pinfunction "C_C") (pintype "passive"))
      (node (ref "Q18") (pin "C") (pinfunction "C_C") (pintype "passive"))
      (node (ref "Q22") (pin "1") (pinfunction "G_1") (pintype "passive"))
      (node (ref "R24") (pin "1") (pinfunction "1_1") (pintype "passive"))
      (node (ref "R26") (pin "1") (pinfunction "1_1") (pintype "passive"))
    )
    (net (code "49") (name "Net-(Q22-S)") (class "Default")
      (node (ref "Q22") (pin "3") (pinfunction "S_3") (pintype "passive"))
      (node (ref "R35") (pin "2") (pinfunction "2_2") (pintype "passive"))
    )
    (net (code "50") (name "Net-(Q23-G)") (class "Default")
      (node (ref "Q23") (pin "1") (pinfunction "G_1") (pintype "passive"))
      (node (ref "R32") (pin "1") (pinfunction "1_1") (pintype "passive"))
    )
    (net (code "51") (name "Net-(Q24-G)") (class "Default")
      (node (ref "Q24") (pin "1") (pinfunction "G_1") (pintype "passive"))
      (node (ref "R33") (pin "1") (pinfunction "1_1") (pintype "passive"))
    )
    (net (code "52") (name "Net-(Q25-D)") (class "Default")
      (node (ref "Q25") (pin "2") (pinfunction "D_2") (pintype "passive"))
      (node (ref "Q27") (pin "3") (pinfunction "S_3") (pintype "passive"))
    )
    (net (code "53") (name "Net-(Q25-G)") (class "Default")
      (node (ref "C2") (pin "1") (pinfunction "1_1") (pintype "passive"))
      (node (ref "C6") (pin "1") (pinfunction "1_1") (pintype "passive"))
      (node (ref "Q13") (pin "C") (pinfunction "C_C") (pintype "passive"))
      (node (ref "Q2") (pin "C") (pinfunction "C_C") (pintype "passive"))
      (node (ref "Q25") (pin "1") (pinfunction "G_1") (pintype "passive"))
      (node (ref "R1") (pin "2") (pinfunction "2_2") (pintype "passive"))
      (node (ref "R20") (pin "2") (pinfunction "2_2") (pintype "passive"))
    )
    (net (code "54") (name "Net-(Q25-S)") (class "Default")
      (node (ref "Q25") (pin "3") (pinfunction "S_3") (pintype "passive"))
      (node (ref "R31") (pin "1") (pinfunction "1_1") (pintype "passive"))
    )
    (net (code "55") (name "Net-(Q26-D)") (class "Default")
      (node (ref "Q26") (pin "2") (pinfunction "D_2") (pintype "passive"))
      (node (ref "Q28") (pin "3") (pinfunction "S_3") (pintype "passive"))
    )
    (net (code "56") (name "Net-(Q26-G)") (class "Default")
      (node (ref "C4") (pin "1") (pinfunction "1_1") (pintype "passive"))
      (node (ref "C6") (pin "2") (pinfunction "2_2") (pintype "passive"))
      (node (ref "Q1") (pin "C") (pinfunction "C_C") (pintype "passive"))
      (node (ref "Q15") (pin "C") (pinfunction "C_C") (pintype "passive"))
      (node (ref "Q26") (pin "1") (pinfunction "G_1") (pintype "passive"))
      (node (ref "R2") (pin "1") (pinfunction "1_1") (pintype "passive"))
      (node (ref "R21") (pin "1") (pinfunction "1_1") (pintype "passive"))
    )
    (net (code "57") (name "Net-(Q26-S)") (class "Default")
      (node (ref "Q26") (pin "3") (pinfunction "S_3") (pintype "passive"))
      (node (ref "R36") (pin "2") (pinfunction "2_2") (pintype "passive"))
    )
    (net (code "58") (name "Net-(Q27-G)") (class "Default")
      (node (ref "Q27") (pin "1") (pinfunction "G_1") (pintype "passive"))
      (node (ref "R22") (pin "1") (pinfunction "1_1") (pintype "passive"))
    )
    (net (code "59") (name "Net-(Q28-G)") (class "Default")
      (node (ref "Q28") (pin "1") (pinfunction "G_1") (pintype "passive"))
      (node (ref "R30") (pin "1") (pinfunction "1_1") (pintype "passive"))
    )
    (net (code "60") (name "Net-(Q33-PadE)") (class "Default")
      (node (ref "Q33") (pin "E") (pinfunction "E_E") (pintype "passive"))
      (node (ref "R42") (pin "2") (pinfunction "2_2") (pintype "passive"))
    )
    (net (code "61") (name "Net-(Q34-PadE)") (class "Default")
      (node (ref "Q34") (pin "E") (pinfunction "E_E") (pintype "passive"))
      (node (ref "R38") (pin "2") (pinfunction "2_2") (pintype "passive"))
    )
    (net (code "62") (name "Net-(Q35-PadE)") (class "Default")
      (node (ref "Q35") (pin "E") (pinfunction "E_E") (pintype "passive"))
      (node (ref "R44") (pin "1") (pinfunction "1_1") (pintype "passive"))
    )
    (net (code "63") (name "Net-(Q36-PadE)") (class "Default")
      (node (ref "Q36") (pin "E") (pinfunction "E_E") (pintype "passive"))
      (node (ref "R40") (pin "1") (pinfunction "1_1") (pintype "passive"))
    )
    (net (code "64") (name "Net-(U$1A-D)") (class "Default")
      (node (ref "Q5") (pin "E") (pinfunction "E_E") (pintype "passive"))
      (node (ref "U$1") (pin "2") (pinfunction "D_2") (pintype "passive"))
    )
    (net (code "65") (name "Net-(U$1A-S)") (class "Default")
      (node (ref "U$1") (pin "3") (pinfunction "S_3") (pintype "passive"))
      (node (ref "VR4") (pin "3") (pinfunction "E_3") (pintype "passive"))
    )
    (net (code "66") (name "Net-(U$1B-D)") (class "Default")
      (node (ref "Q6") (pin "E") (pinfunction "E_E") (pintype "passive"))
      (node (ref "U$1") (pin "5") (pinfunction "D_5") (pintype "passive"))
    )
    (net (code "67") (name "Net-(U$1B-S)") (class "Default")
      (node (ref "U$1") (pin "6") (pinfunction "S_6") (pintype "passive"))
      (node (ref "VR4") (pin "1") (pinfunction "A_1") (pintype "passive"))
    )
    (net (code "68") (name "Net-(U$3A-D)") (class "Default")
      (node (ref "Q29") (pin "E") (pinfunction "E_E") (pintype "passive"))
      (node (ref "U$3") (pin "2") (pinfunction "D_2") (pintype "passive"))
    )
    (net (code "69") (name "Net-(U$3A-G)") (class "Default")
      (node (ref "C1") (pin "1") (pinfunction "1_1") (pintype "passive"))
      (node (ref "C11") (pin "2") (pinfunction "2_2") (pintype "passive"))
      (node (ref "R3") (pin "2") (pinfunction "2_2") (pintype "passive"))
      (node (ref "R4") (pin "1") (pinfunction "1_1") (pintype "passive"))
      (node (ref "U$3") (pin "1") (pinfunction "G_1") (pintype "passive"))
      (node (ref "U$4") (pin "1") (pinfunction "G_1") (pintype "passive"))
    )
    (net (code "70") (name "Net-(U$3A-S)") (class "Default")
      (node (ref "D11") (pin "A") (pinfunction "A_A") (pintype "passive"))
      (node (ref "R43") (pin "1") (pinfunction "1_1") (pintype "passive"))
      (node (ref "U$3") (pin "3") (pinfunction "S_3") (pintype "passive"))
      (node (ref "U$3") (pin "6") (pinfunction "S_6") (pintype "passive"))
    )
    (net (code "71") (name "Net-(U$3B-D)") (class "Default")
      (node (ref "Q31") (pin "E") (pinfunction "E_E") (pintype "passive"))
      (node (ref "U$3") (pin "5") (pinfunction "D_5") (pintype "passive"))
    )
    (net (code "72") (name "Net-(U$3B-G)") (class "Default")
      (node (ref "C10") (pin "1") (pinfunction "1_1") (pintype "passive"))
      (node (ref "C12") (pin "2") (pinfunction "2_2") (pintype "passive"))
      (node (ref "R41") (pin "1") (pinfunction "1_1") (pintype "passive"))
      (node (ref "U$3") (pin "4") (pinfunction "G_4") (pintype "passive"))
      (node (ref "U$4") (pin "4") (pinfunction "G_4") (pintype "passive"))
    )
    (net (code "73") (name "Net-(U$4A-D)") (class "Default")
      (node (ref "Q30") (pin "E") (pinfunction "E_E") (pintype "passive"))
      (node (ref "U$4") (pin "2") (pinfunction "D_2") (pintype "passive"))
    )
    (net (code "74") (name "Net-(U$4A-S)") (class "Default")
      (node (ref "D12") (pin "C") (pinfunction "C_C") (pintype "passive"))
      (node (ref "R43") (pin "2") (pinfunction "2_2") (pintype "passive"))
      (node (ref "U$4") (pin "3") (pinfunction "S_3") (pintype "passive"))
      (node (ref "U$4") (pin "6") (pinfunction "S_6") (pintype "passive"))
    )
    (net (code "75") (name "Net-(U$4B-D)") (class "Default")
      (node (ref "Q32") (pin "E") (pinfunction "E_E") (pintype "passive"))
      (node (ref "U$4") (pin "5") (pinfunction "D_5") (pintype "passive"))
    )
    (net (code "76") (name "Net-(U$5A-D)") (class "Default")
      (node (ref "Q8") (pin "E") (pinfunction "E_E") (pintype "passive"))
      (node (ref "U$5") (pin "2") (pinfunction "D_2") (pintype "passive"))
    )
    (net (code "77") (name "Net-(U$5A-S)") (class "Default")
      (node (ref "R8") (pin "1") (pinfunction "1_1") (pintype "passive"))
      (node (ref "U$5") (pin "3") (pinfunction "S_3") (pintype "passive"))
    )
    (net (code "78") (name "Net-(U$5B-D)") (class "Default")
      (node (ref "Q7") (pin "E") (pinfunction "E_E") (pintype "passive"))
      (node (ref "U$5") (pin "5") (pinfunction "D_5") (pintype "passive"))
    )
    (net (code "79") (name "Net-(U$5B-S)") (class "Default")
      (node (ref "R7") (pin "2") (pinfunction "2_2") (pintype "passive"))
      (node (ref "U$5") (pin "6") (pinfunction "S_6") (pintype "passive"))
    )
    (net (code "80") (name "Net-(VR1-A)") (class "Default")
      (node (ref "D1") (pin "A") (pinfunction "A_A") (pintype "passive"))
      (node (ref "VR1") (pin "1") (pinfunction "A_1") (pintype "passive"))
      (node (ref "VR1") (pin "2") (pinfunction "S_2") (pintype "passive"))
      (node (ref "VR4") (pin "2") (pinfunction "S_2") (pintype "passive"))
    )
    (net (code "81") (name "Net-(VR1-E)") (class "Default")
      (node (ref "D2") (pin "C") (pinfunction "C_C") (pintype "passive"))
      (node (ref "R7") (pin "1") (pinfunction "1_1") (pintype "passive"))
      (node (ref "R8") (pin "2") (pinfunction "2_2") (pintype "passive"))
      (node (ref "VR1") (pin "3") (pinfunction "E_3") (pintype "passive"))
    )
    (net (code "82") (name "Net-(VR2-A)") (class "Default")
      (node (ref "Q2") (pin "B") (pinfunction "B_B") (pintype "passive"))
      (node (ref "R1") (pin "1") (pinfunction "1_1") (pintype "passive"))
      (node (ref "VR2") (pin "1") (pinfunction "A_1") (pintype "passive"))
      (node (ref "VR2") (pin "2") (pinfunction "S_2") (pintype "passive"))
    )
    (net (code "83") (name "Net-(VR2-E)") (class "Default")
      (node (ref "R5") (pin "2") (pinfunction "2_2") (pintype "passive"))
      (node (ref "VR2") (pin "3") (pinfunction "E_3") (pintype "passive"))
    )
    (net (code "84") (name "Net-(VR3-A)") (class "Default")
      (node (ref "Q17") (pin "B") (pinfunction "B_B") (pintype "passive"))
      (node (ref "R25") (pin "1") (pinfunction "1_1") (pintype "passive"))
      (node (ref "VR3") (pin "1") (pinfunction "A_1") (pintype "passive"))
      (node (ref "VR3") (pin "2") (pinfunction "S_2") (pintype "passive"))
    )
    (net (code "85") (name "Net-(VR3-E)") (class "Default")
      (node (ref "R27") (pin "2") (pinfunction "2_2") (pintype "passive"))
      (node (ref "VR3") (pin "3") (pinfunction "E_3") (pintype "passive"))
    )
    (net (code "86") (name "V+") (class "Default")
      (node (ref "CR1") (pin "ANODE") (pinfunction "ANODE_ANODE") (pintype "passive"))
      (node (ref "CR3") (pin "ANODE") (pinfunction "ANODE_ANODE") (pintype "passive"))
      (node (ref "Q19") (pin "1") (pinfunction "D_1") (pintype "passive"))
      (node (ref "Q23") (pin "2") (pinfunction "D_2") (pintype "passive"))
      (node (ref "Q27") (pin "2") (pinfunction "D_2") (pintype "passive"))
      (node (ref "Q3") (pin "1") (pinfunction "D_1") (pintype "passive"))
      (node (ref "R10") (pin "1") (pinfunction "1_1") (pintype "passive"))
      (node (ref "R14") (pin "1") (pinfunction "1_1") (pintype "passive"))
      (node (ref "R37") (pin "1") (pinfunction "1_1") (pintype "passive"))
      (node (ref "R38") (pin "1") (pinfunction "1_1") (pintype "passive"))
      (node (ref "R42") (pin "1") (pinfunction "1_1") (pintype "passive"))
      (node (ref "R9") (pin "1") (pinfunction "1_1") (pintype "passive"))
    )
    (net (code "87") (name "V-") (class "Default")
      (node (ref "CR2") (pin "CATHODE") (pinfunction "CATHODE_CATHODE") (pintype "passive"))
      (node (ref "CR4") (pin "CATHODE") (pinfunction "CATHODE_CATHODE") (pintype "passive"))
      (node (ref "Q20") (pin "3") (pinfunction "G_3") (pintype "passive"))
      (node (ref "Q24") (pin "2") (pinfunction "D_2") (pintype "passive"))
      (node (ref "Q28") (pin "2") (pinfunction "D_2") (pintype "passive"))
      (node (ref "Q4") (pin "3") (pinfunction "G_3") (pintype "passive"))
      (node (ref "R11") (pin "2") (pinfunction "2_2") (pintype "passive"))
      (node (ref "R12") (pin "2") (pinfunction "2_2") (pintype "passive"))
      (node (ref "R13") (pin "2") (pinfunction "2_2") (pintype "passive"))
      (node (ref "R15") (pin "2") (pinfunction "2_2") (pintype "passive"))
      (node (ref "R29") (pin "2") (pinfunction "2_2") (pintype "passive"))
      (node (ref "R39") (pin "2") (pinfunction "2_2") (pintype "passive"))
      (node (ref "R40") (pin "2") (pinfunction "2_2") (pintype "passive"))
      (node (ref "R44") (pin "2") (pinfunction "2_2") (pintype "passive"))
    )
    (net (code "88") (name "unconnected-(R45-Pad2)") (class "Default")
      (node (ref "R45") (pin "2") (pinfunction "2_2") (pintype "passive"))
    )
    (net (code "89") (name "unconnected-(R46-Pad2)") (class "Default")
      (node (ref "R46") (pin "2") (pinfunction "2_2") (pintype "passive"))
    )
  )
)
